# charging_circuit.net
KiCad netlist of a schematic drawn in EAGLE
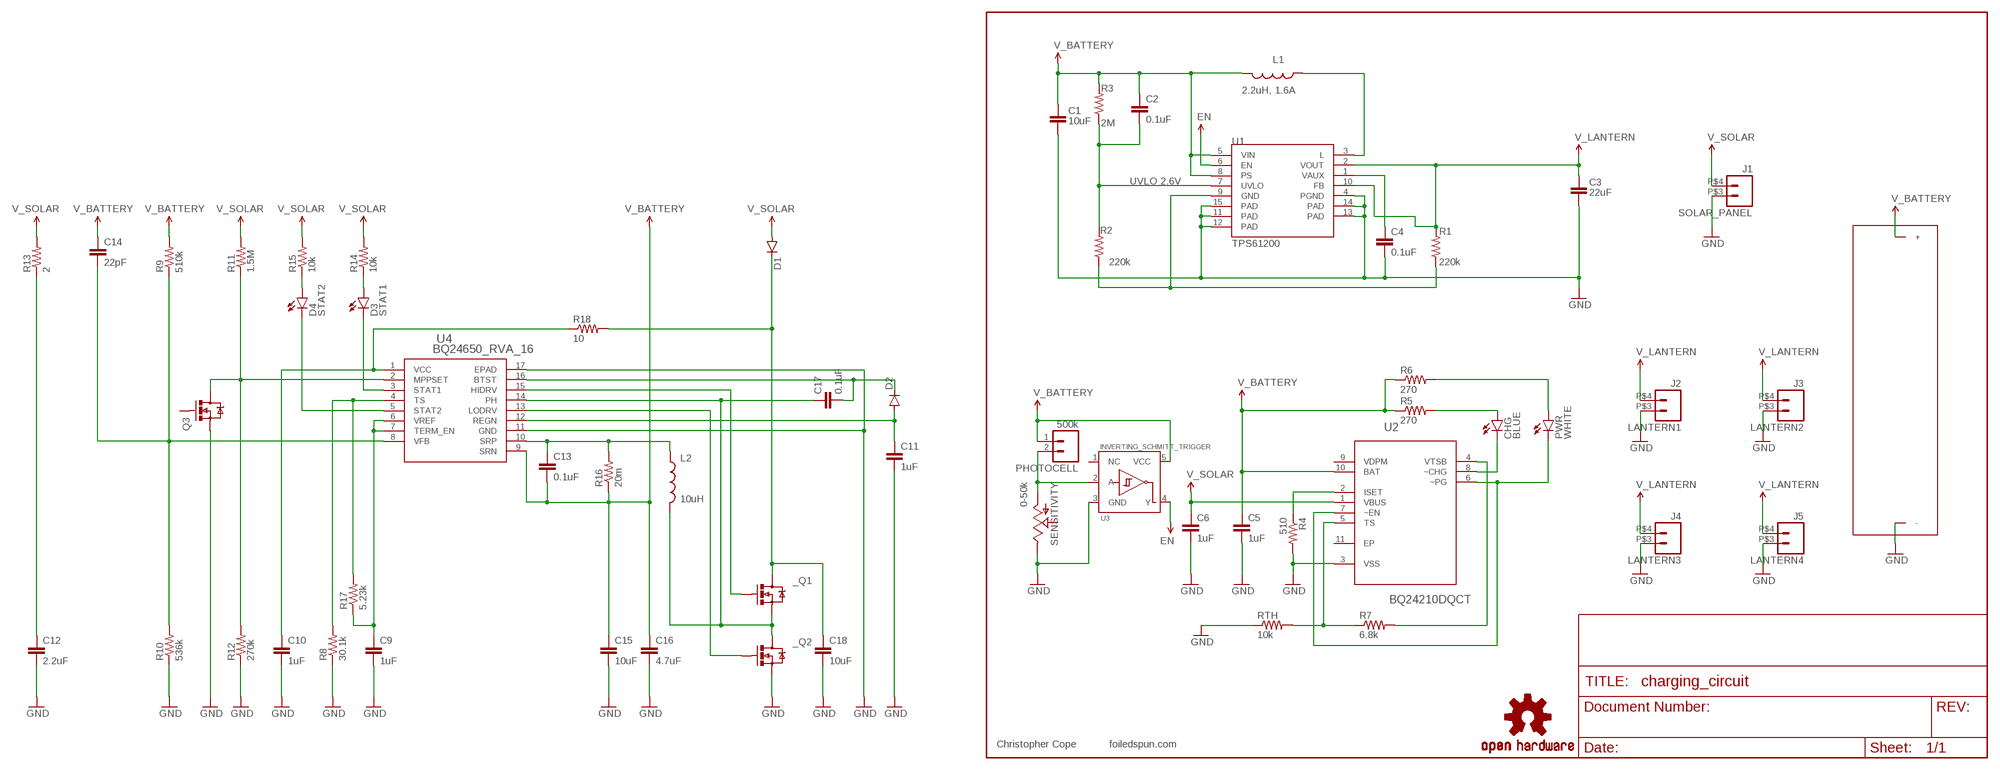
[diagram p0: schematic, sheet 1]

(export (version "E")
  (design (tool "Eeschema 10.0.6"))
  (components
    (comp (ref "C1")
      (value "10uF")
      (footprint "eagle-import:1206")
      (libsource (lib "eagle-import") (part "CAP1206"))
    )
    (comp (ref "C2")
      (value "0.1uF")
      (footprint "eagle-import:0402-CAP")
      (libsource (lib "eagle-import") (part "CAP0402-CAP"))
    )
    (comp (ref "C3")
      (value "22uF")
      (footprint "eagle-import:0805")
      (libsource (lib "eagle-import") (part "CAP0805"))
    )
    (comp (ref "C4")
      (value "0.1uF")
      (footprint "eagle-import:0402-CAP")
      (libsource (lib "eagle-import") (part "CAP0402-CAP"))
    )
    (comp (ref "C5")
      (value "1uF")
      (footprint "eagle-import:0805")
      (libsource (lib "eagle-import") (part "1UF-25V-10%(0805)"))
    )
    (comp (ref "C6")
      (value "1uF")
      (footprint "eagle-import:0805")
      (libsource (lib "eagle-import") (part "1UF-25V-10%(0805)"))
    )
    (comp (ref "C9")
      (value "1uF")
      (footprint "eagle-import:0402-CAP")
      (libsource (lib "eagle-import") (part "CAP0402-CAP"))
    )
    (comp (ref "C10")
      (value "1uF")
      (footprint "eagle-import:0402-CAP")
      (libsource (lib "eagle-import") (part "CAP0402-CAP"))
    )
    (comp (ref "C11")
      (value "1uF")
      (footprint "eagle-import:0402-CAP")
      (libsource (lib "eagle-import") (part "CAP0402-CAP"))
    )
    (comp (ref "C12")
      (value "2.2uF")
      (footprint "eagle-import:0402-CAP")
      (libsource (lib "eagle-import") (part "CAP0402-CAP"))
    )
    (comp (ref "C13")
      (value "0.1uF")
      (footprint "eagle-import:0805")
      (libsource (lib "eagle-import") (part "SparkFun-Passives_CAP0805"))
    )
    (comp (ref "C14")
      (value "22pF")
      (footprint "eagle-import:0603-CAP")
      (libsource (lib "eagle-import") (part "SparkFun-Passives_CAP0603-CAP"))
    )
    (comp (ref "C15")
      (value "10uF")
      (footprint "eagle-import:1210")
      (libsource (lib "eagle-import") (part "SparkFun-Passives_CAP1210"))
    )
    (comp (ref "C16")
      (value "4.7uF")
      (footprint "eagle-import:1210")
      (libsource (lib "eagle-import") (part "SparkFun-Passives_CAP1210"))
    )
    (comp (ref "C17")
      (value "0.1uF")
      (footprint "eagle-import:0805")
      (libsource (lib "eagle-import") (part "SparkFun-Passives_CAP0805"))
    )
    (comp (ref "C18")
      (value "10uF")
      (footprint "eagle-import:1210")
      (libsource (lib "eagle-import") (part "SparkFun-Passives_CAP1210"))
    )
    (comp (ref "CHG")
      (value "BLUE")
      (footprint "eagle-import:LED-0603")
      (libsource (lib "eagle-import") (part "LED0603"))
    )
    (comp (ref "D1")
      (value "DIODEPDS1040")
      (footprint "eagle-import:POWERDI-5")
      (libsource (lib "eagle-import") (part "DIODEPDS1040"))
    )
    (comp (ref "D2")
      (value "DIODESOT23")
      (footprint "eagle-import:SOT23-3")
      (libsource (lib "eagle-import") (part "SparkFun-DiscreteSemi_DIODESOT23"))
    )
    (comp (ref "D3")
      (value "STAT1")
      (footprint "eagle-import:LED-0603")
      (libsource (lib "eagle-import") (part "LED-GREEN0603"))
    )
    (comp (ref "D4")
      (value "STAT2")
      (footprint "eagle-import:LED-0603")
      (libsource (lib "eagle-import") (part "LED-GREEN0603"))
    )
    (comp (ref "L1")
      (value "2.2uH, 1.6A")
      (footprint "eagle-import:1210")
      (libsource (lib "eagle-import") (part "INDUCTOR1210"))
    )
    (comp (ref "L2")
      (value "10uH")
      (footprint "eagle-import:IHLP-2525CZ-01")
      (libsource (lib "eagle-import") (part "INDUCTORIHLP-2525CZ-01"))
    )
    (comp (ref "LANTERN1")
      (value "J2")
      (footprint "eagle-import:2-1445100-2")
      (libsource (lib "eagle-import") (part "MICRO_MATE-N-LOCK"))
    )
    (comp (ref "LANTERN2")
      (value "J3")
      (footprint "eagle-import:2-1445100-2")
      (libsource (lib "eagle-import") (part "MICRO_MATE-N-LOCK"))
    )
    (comp (ref "LANTERN3")
      (value "J4")
      (footprint "eagle-import:2-1445100-2")
      (libsource (lib "eagle-import") (part "MICRO_MATE-N-LOCK"))
    )
    (comp (ref "LANTERN4")
      (value "J5")
      (footprint "eagle-import:2-1445100-2")
      (libsource (lib "eagle-import") (part "MICRO_MATE-N-LOCK"))
    )
    (comp (ref "LOGO2")
      (value "OSHW-LOGOL")
      (footprint "eagle-import:OSHW-LOGO-L")
      (libsource (lib "eagle-import") (part "OSHW-LOGOL"))
    )
    (comp (ref "PHOTOCELL")
      (value "500k")
      (footprint "eagle-import:1X02_SMD")
      (libsource (lib "eagle-import") (part "M021X02_SMD"))
    )
    (comp (ref "PWR")
      (value "WHITE")
      (footprint "eagle-import:LED-0603")
      (libsource (lib "eagle-import") (part "LED0603"))
    )
    (comp (ref "Q3")
      (value "MOSFET-NCHANNEL")
      (footprint "eagle-import:SOT23-3")
      (libsource (lib "eagle-import") (part "MOSFET-NCHANNEL"))
    )
    (comp (ref "R1")
      (value "220k")
      (footprint "eagle-import:0402-RES")
      (libsource (lib "eagle-import") (part "RESISTOR0402-RES"))
    )
    (comp (ref "R2")
      (value "220k")
      (footprint "eagle-import:0402-RES")
      (libsource (lib "eagle-import") (part "RESISTOR0402-RES"))
    )
    (comp (ref "R3")
      (value "2M")
      (footprint "eagle-import:0402-RES")
      (libsource (lib "eagle-import") (part "RESISTOR0402-RES"))
    )
    (comp (ref "R4")
      (value "510")
      (footprint "eagle-import:0402-RES")
      (libsource (lib "eagle-import") (part "SparkFun-Resistors_RESISTOR0402-RES"))
    )
    (comp (ref "R5")
      (value "270")
      (footprint "eagle-import:0402-RES")
      (libsource (lib "eagle-import") (part "SparkFun-Resistors_RESISTOR0402-RES"))
    )
    (comp (ref "R6")
      (value "270")
      (footprint "eagle-import:0402-RES")
      (libsource (lib "eagle-import") (part "SparkFun-Resistors_RESISTOR0402-RES"))
    )
    (comp (ref "R7")
      (value "6.8k")
      (footprint "eagle-import:0402-RES")
      (libsource (lib "eagle-import") (part "SparkFun-Resistors_RESISTOR0402-RES"))
    )
    (comp (ref "R8")
      (value "30.1k")
      (footprint "eagle-import:0402-RES")
      (libsource (lib "eagle-import") (part "SparkFun-Passives_RESISTOR0402-RES"))
    )
    (comp (ref "R9")
      (value "510k")
      (footprint "eagle-import:0402-RES")
      (libsource (lib "eagle-import") (part "RESISTOR0402-RES"))
    )
    (comp (ref "R10")
      (value "536k")
      (footprint "eagle-import:0402-RES")
      (libsource (lib "eagle-import") (part "RESISTOR0402-RES"))
    )
    (comp (ref "R11")
      (value "1.5M")
      (footprint "eagle-import:0402-RES")
      (libsource (lib "eagle-import") (part "RESISTOR0402-RES"))
    )
    (comp (ref "R12")
      (value "270k")
      (footprint "eagle-import:0402-RES")
      (libsource (lib "eagle-import") (part "RESISTOR0402-RES"))
    )
    (comp (ref "R13")
      (value "2")
      (footprint "eagle-import:0402-RES")
      (libsource (lib "eagle-import") (part "RESISTOR0402-RES"))
    )
    (comp (ref "R14")
      (value "10k")
      (footprint "eagle-import:0402-RES")
      (libsource (lib "eagle-import") (part "SparkFun-Passives_RESISTOR0402-RES"))
    )
    (comp (ref "R15")
      (value "10k")
      (footprint "eagle-import:0402-RES")
      (libsource (lib "eagle-import") (part "SparkFun-Passives_RESISTOR0402-RES"))
    )
    (comp (ref "R16")
      (value "20m")
      (footprint "eagle-import:1206")
      (libsource (lib "eagle-import") (part "SparkFun-Passives_RESISTOR1206"))
    )
    (comp (ref "R17")
      (value "5.23k")
      (footprint "eagle-import:0402-RES")
      (libsource (lib "eagle-import") (part "SparkFun-Passives_RESISTOR0402-RES"))
    )
    (comp (ref "R18")
      (value "10")
      (footprint "eagle-import:1206")
      (libsource (lib "eagle-import") (part "SparkFun-Passives_RESISTOR1206"))
    )
    (comp (ref "RTH")
      (value "10k")
      (footprint "eagle-import:0402-RES")
      (libsource (lib "eagle-import") (part "SparkFun-Resistors_RESISTOR0402-RES"))
    )
    (comp (ref "SENSITIVITY")
      (value "0-50k")
      (footprint "eagle-import:TRIM_POT-SMD")
      (libsource (lib "eagle-import") (part "POTTRIM_POT-SMD"))
    )
    (comp (ref "SOLAR_PANEL")
      (value "J1")
      (footprint "eagle-import:2-1445100-2")
      (libsource (lib "eagle-import") (part "MICRO_MATE-N-LOCK"))
    )
    (comp (ref "U$1")
      (value "18650-HOLDER")
      (footprint "eagle-import:18650")
      (libsource (lib "eagle-import") (part "18650-HOLDER"))
    )
    (comp (ref "U1")
      (value "TPS61200")
      (footprint "eagle-import:QFN-10_PAD")
      (libsource (lib "eagle-import") (part "TPS61200"))
    )
    (comp (ref "U2")
      (value "BQ24210DQCT")
      (footprint "eagle-import:SON50P200X300X80-11N")
      (libsource (lib "eagle-import") (part "BQ24210DQCT"))
    )
    (comp (ref "U3")
      (value "INVERTING_SCHMITT_TRIGGER")
      (footprint "eagle-import:SC-70-5(DCK)")
      (libsource (lib "eagle-import") (part "INVERTING_SCHMITT_TRIGGER"))
    )
    (comp (ref "U4")
      (value "BQ24650_RVA_16")
      (footprint "eagle-import:RVA16_2P14X2P14")
      (fields
        (field (name "GENERIC_PART_NUMBER") "BQ24650")
        (field (name "MANUFACTURER") "Texas Instruments")
      )
      (libsource (lib "eagle-import") (part "BQ24650_RVA_16"))
    )
    (comp (ref "_")
      (value "MOSFET-DUAL_NCHANNEL")
      (footprint "eagle-import:POWERPAK_SO-8")
      (libsource (lib "eagle-import") (part "MOSFET-DUAL_NCHANNEL"))
    )
  )
  (nets
    (net (code "1") (name "EN") (class "Default")
      (node (ref "U1") (pin "6") (pinfunction "EN_6") (pintype "input"))
      (node (ref "U3") (pin "4") (pinfunction "Y_4") (pintype "bidirectional"))
    )
    (net (code "2") (name "GND") (class "Default")
      (node (ref "C1") (pin "2") (pinfunction "2_2") (pintype "passive"))
      (node (ref "C10") (pin "2") (pinfunction "2_2") (pintype "passive"))
      (node (ref "C11") (pin "2") (pinfunction "2_2") (pintype "passive"))
      (node (ref "C12") (pin "2") (pinfunction "2_2") (pintype "passive"))
      (node (ref "C15") (pin "2") (pinfunction "2_2") (pintype "passive"))
      (node (ref "C16") (pin "2") (pinfunction "2_2") (pintype "passive"))
      (node (ref "C18") (pin "2") (pinfunction "2_2") (pintype "passive"))
      (node (ref "C3") (pin "2") (pinfunction "2_2") (pintype "passive"))
      (node (ref "C4") (pin "2") (pinfunction "2_2") (pintype "passive"))
      (node (ref "C5") (pin "2") (pinfunction "2_2") (pintype "passive"))
      (node (ref "C6") (pin "2") (pinfunction "2_2") (pintype "passive"))
      (node (ref "C9") (pin "2") (pinfunction "2_2") (pintype "passive"))
      (node (ref "LANTERN1") (pin "P$3") (pinfunction "2_P$3") (pintype "passive"))
      (node (ref "LANTERN2") (pin "P$3") (pinfunction "2_P$3") (pintype "passive"))
      (node (ref "LANTERN3") (pin "P$3") (pinfunction "2_P$3") (pintype "passive"))
      (node (ref "LANTERN4") (pin "P$3") (pinfunction "2_P$3") (pintype "passive"))
      (node (ref "Q3") (pin "2") (pinfunction "S_2") (pintype "passive"))
      (node (ref "R10") (pin "1") (pinfunction "1_1") (pintype "passive"))
      (node (ref "R12") (pin "1") (pinfunction "1_1") (pintype "passive"))
      (node (ref "R4") (pin "2") (pinfunction "2_2") (pintype "passive"))
      (node (ref "R8") (pin "1") (pinfunction "1_1") (pintype "passive"))
      (node (ref "RTH") (pin "1") (pinfunction "1_1") (pintype "passive"))
      (node (ref "SENSITIVITY") (pin "P$3") (pinfunction "E_P$3") (pintype "passive"))
      (node (ref "SOLAR_PANEL") (pin "P$3") (pinfunction "2_P$3") (pintype "passive"))
      (node (ref "U$1") (pin "-") (pinfunction "-_-") (pintype "power_in"))
      (node (ref "U1") (pin "11") (pinfunction "PAD_11") (pintype "power_in"))
      (node (ref "U1") (pin "12") (pinfunction "PAD_12") (pintype "power_in"))
      (node (ref "U1") (pin "13") (pinfunction "PAD_13") (pintype "power_in"))
      (node (ref "U1") (pin "14") (pinfunction "PAD_14") (pintype "power_in"))
      (node (ref "U1") (pin "15") (pinfunction "PAD_15") (pintype "power_in"))
      (node (ref "U1") (pin "4") (pinfunction "PGND_4") (pintype "power_in"))
      (node (ref "U2") (pin "3") (pinfunction "VSS_3") (pintype "passive"))
      (node (ref "U3") (pin "3") (pinfunction "GND_3") (pintype "bidirectional"))
      (node (ref "U4") (pin "11") (pinfunction "GND_11") (pintype "power_in"))
      (node (ref "U4") (pin "17") (pinfunction "EPAD_17") (pintype "power_in"))
      (node (ref "_") (pin "P$3$S2") (pinfunction "S_P$3$S2") (pintype "passive"))
    )
    (net (code "3") (name "Net-(C12-Pad1)") (class "Default")
      (node (ref "C12") (pin "1") (pinfunction "1_1") (pintype "passive"))
      (node (ref "R13") (pin "1") (pinfunction "1_1") (pintype "passive"))
    )
    (net (code "4") (name "Net-(CHG-PadA)") (class "Default")
      (node (ref "CHG") (pin "A") (pinfunction "A_A") (pintype "passive"))
      (node (ref "R5") (pin "2") (pinfunction "2_2") (pintype "passive"))
    )
    (net (code "5") (name "Net-(D1-C)") (class "Default")
      (node (ref "C18") (pin "1") (pinfunction "1_1") (pintype "passive"))
      (node (ref "D1") (pin "P$3") (pinfunction "C_P$3") (pintype "passive"))
      (node (ref "R18") (pin "2") (pinfunction "2_2") (pintype "passive"))
      (node (ref "_") (pin "P$7$D1") (pinfunction "D_P$7$D1") (pintype "passive"))
      (node (ref "_") (pin "P$8$D1") (pinfunction "D_P$8$D1") (pintype "passive"))
      (node (ref "_") (pin "P$D1") (pinfunction "D_P$D1") (pintype "passive"))
    )
    (net (code "6") (name "Net-(D2-A)") (class "Default")
      (node (ref "C11") (pin "1") (pinfunction "1_1") (pintype "passive"))
      (node (ref "D2") (pin "1") (pinfunction "A_1") (pintype "passive"))
      (node (ref "U4") (pin "12") (pinfunction "REGN_12") (pintype "power_in"))
    )
    (net (code "7") (name "Net-(D2-C)") (class "Default")
      (node (ref "C17") (pin "2") (pinfunction "2_2") (pintype "passive"))
      (node (ref "D2") (pin "3") (pinfunction "C_3") (pintype "passive"))
      (node (ref "U4") (pin "16") (pinfunction "BTST_16") (pintype "power_in"))
    )
    (net (code "8") (name "Net-(D3-PadA)") (class "Default")
      (node (ref "D3") (pin "A") (pinfunction "A_A") (pintype "passive"))
      (node (ref "R14") (pin "1") (pinfunction "1_1") (pintype "passive"))
    )
    (net (code "9") (name "Net-(D4-PadA)") (class "Default")
      (node (ref "D4") (pin "A") (pinfunction "A_A") (pintype "passive"))
      (node (ref "R15") (pin "1") (pinfunction "1_1") (pintype "passive"))
    )
    (net (code "10") (name "Net-(L2-1)") (class "Default")
      (node (ref "C13") (pin "1") (pinfunction "1_1") (pintype "passive"))
      (node (ref "L2") (pin "P$1") (pinfunction "1_P$1") (pintype "passive"))
      (node (ref "R16") (pin "2") (pinfunction "2_2") (pintype "passive"))
      (node (ref "U4") (pin "10") (pinfunction "SRP_10") (pintype "bidirectional"))
    )
    (net (code "11") (name "Net-(L2-2)") (class "Default")
      (node (ref "C17") (pin "1") (pinfunction "1_1") (pintype "passive"))
      (node (ref "L2") (pin "P$2") (pinfunction "2_P$2") (pintype "passive"))
      (node (ref "U4") (pin "14") (pinfunction "PH_14") (pintype "power_in"))
      (node (ref "_") (pin "P$1$S1") (pinfunction "S_P$1$S1") (pintype "passive"))
      (node (ref "_") (pin "P$5$D2") (pinfunction "D_P$5$D2") (pintype "passive"))
      (node (ref "_") (pin "P$6$D2") (pinfunction "D_P$6$D2") (pintype "passive"))
      (node (ref "_") (pin "P$D2") (pinfunction "D_P$D2") (pintype "passive"))
    )
    (net (code "12") (name "Net-(PWR-PadA)") (class "Default")
      (node (ref "PWR") (pin "A") (pinfunction "A_A") (pintype "passive"))
      (node (ref "R6") (pin "2") (pinfunction "2_2") (pintype "passive"))
    )
    (net (code "13") (name "Net-(Q3-D)") (class "Default")
      (node (ref "Q3") (pin "3") (pinfunction "D_3") (pintype "passive"))
      (node (ref "R11") (pin "1") (pinfunction "1_1") (pintype "passive"))
      (node (ref "R12") (pin "2") (pinfunction "2_2") (pintype "passive"))
      (node (ref "U4") (pin "2") (pinfunction "MPPSET_2") (pintype "input"))
    )
    (net (code "14") (name "Net-(SENSITIVITY-A)") (class "Default")
      (node (ref "PHOTOCELL") (pin "2") (pinfunction "2_2") (pintype "passive"))
      (node (ref "SENSITIVITY") (pin "P$1") (pinfunction "A_P$1") (pintype "passive"))
      (node (ref "U3") (pin "2") (pinfunction "A_2") (pintype "bidirectional"))
    )
    (net (code "15") (name "Net-(U1-GND)") (class "Default")
      (node (ref "R1") (pin "1") (pinfunction "1_1") (pintype "passive"))
      (node (ref "R2") (pin "1") (pinfunction "1_1") (pintype "passive"))
      (node (ref "U1") (pin "9") (pinfunction "GND_9") (pintype "power_in"))
    )
    (net (code "16") (name "Net-(U1-L)") (class "Default")
      (node (ref "L1") (pin "1") (pinfunction "1_1") (pintype "passive"))
      (node (ref "U1") (pin "3") (pinfunction "L_3") (pintype "passive"))
    )
    (net (code "17") (name "Net-(U1-UVLO)") (class "Default")
      (node (ref "C2") (pin "2") (pinfunction "2_2") (pintype "passive"))
      (node (ref "R2") (pin "2") (pinfunction "2_2") (pintype "passive"))
      (node (ref "R3") (pin "1") (pinfunction "1_1") (pintype "passive"))
      (node (ref "U1") (pin "7") (pinfunction "UVLO_7") (pintype "passive"))
    )
    (net (code "18") (name "Net-(U1-VAUX)") (class "Default")
      (node (ref "C4") (pin "1") (pinfunction "1_1") (pintype "passive"))
      (node (ref "U1") (pin "1") (pinfunction "VAUX_1") (pintype "passive"))
    )
    (net (code "19") (name "Net-(U2-ISET)") (class "Default")
      (node (ref "R4") (pin "1") (pinfunction "1_1") (pintype "passive"))
      (node (ref "U2") (pin "2") (pinfunction "ISET_2") (pintype "input"))
    )
    (net (code "20") (name "Net-(U2-TS)") (class "Default")
      (node (ref "R7") (pin "1") (pinfunction "1_1") (pintype "passive"))
      (node (ref "RTH") (pin "2") (pinfunction "2_2") (pintype "passive"))
      (node (ref "U2") (pin "5") (pinfunction "TS_5") (pintype "input"))
    )
    (net (code "21") (name "Net-(U2-VTSB)") (class "Default")
      (node (ref "R7") (pin "2") (pinfunction "2_2") (pintype "passive"))
      (node (ref "U2") (pin "4") (pinfunction "VTSB_4") (pintype "output"))
    )
    (net (code "22") (name "Net-(U2-~{CHG})") (class "Default")
      (node (ref "CHG") (pin "C") (pinfunction "C_C") (pintype "passive"))
      (node (ref "U2") (pin "8") (pinfunction "~{CHG}_8") (pintype "output"))
    )
    (net (code "23") (name "Net-(U2-~{EN})") (class "Default")
      (node (ref "PWR") (pin "C") (pinfunction "C_C") (pintype "passive"))
      (node (ref "U2") (pin "6") (pinfunction "~{PG}_6") (pintype "output"))
      (node (ref "U2") (pin "7") (pinfunction "~{EN}_7") (pintype "input"))
    )
    (net (code "24") (name "Net-(U4-HIDRV)") (class "Default")
      (node (ref "U4") (pin "15") (pinfunction "HIDRV_15") (pintype "output"))
      (node (ref "_") (pin "P$2$G1") (pinfunction "G_P$2$G1") (pintype "passive"))
    )
    (net (code "25") (name "Net-(U4-LODRV)") (class "Default")
      (node (ref "U4") (pin "13") (pinfunction "LODRV_13") (pintype "output"))
      (node (ref "_") (pin "P$4$G2") (pinfunction "G_P$4$G2") (pintype "passive"))
    )
    (net (code "26") (name "Net-(U4-STAT1)") (class "Default")
      (node (ref "D3") (pin "C") (pinfunction "C_C") (pintype "passive"))
      (node (ref "U4") (pin "3") (pinfunction "STAT1_3") (pintype "output"))
    )
    (net (code "27") (name "Net-(U4-STAT2)") (class "Default")
      (node (ref "D4") (pin "C") (pinfunction "C_C") (pintype "passive"))
      (node (ref "U4") (pin "5") (pinfunction "STAT2_5") (pintype "output"))
    )
    (net (code "28") (name "Net-(U4-TERM_EN)") (class "Default")
      (node (ref "C9") (pin "1") (pinfunction "1_1") (pintype "passive"))
      (node (ref "R17") (pin "1") (pinfunction "1_1") (pintype "passive"))
      (node (ref "U4") (pin "6") (pinfunction "VREF_6") (pintype "power_in"))
      (node (ref "U4") (pin "7") (pinfunction "TERM_EN_7") (pintype "input"))
    )
    (net (code "29") (name "Net-(U4-TS)") (class "Default")
      (node (ref "R17") (pin "2") (pinfunction "2_2") (pintype "passive"))
      (node (ref "R8") (pin "2") (pinfunction "2_2") (pintype "passive"))
      (node (ref "U4") (pin "4") (pinfunction "TS_4") (pintype "input"))
    )
    (net (code "30") (name "Net-(U4-VCC)") (class "Default")
      (node (ref "C10") (pin "1") (pinfunction "1_1") (pintype "passive"))
      (node (ref "R18") (pin "1") (pinfunction "1_1") (pintype "passive"))
      (node (ref "U4") (pin "1") (pinfunction "VCC_1") (pintype "power_in"))
    )
    (net (code "31") (name "Net-(U4-VFB)") (class "Default")
      (node (ref "C14") (pin "2") (pinfunction "2_2") (pintype "passive"))
      (node (ref "R10") (pin "2") (pinfunction "2_2") (pintype "passive"))
      (node (ref "R9") (pin "1") (pinfunction "1_1") (pintype "passive"))
      (node (ref "U4") (pin "8") (pinfunction "VFB_8") (pintype "input"))
    )
    (net (code "32") (name "V_BATTERY") (class "Default")
      (node (ref "C1") (pin "1") (pinfunction "1_1") (pintype "passive"))
      (node (ref "C13") (pin "2") (pinfunction "2_2") (pintype "passive"))
      (node (ref "C14") (pin "1") (pinfunction "1_1") (pintype "passive"))
      (node (ref "C15") (pin "1") (pinfunction "1_1") (pintype "passive"))
      (node (ref "C16") (pin "1") (pinfunction "1_1") (pintype "passive"))
      (node (ref "C2") (pin "1") (pinfunction "1_1") (pintype "passive"))
      (node (ref "C5") (pin "1") (pinfunction "1_1") (pintype "passive"))
      (node (ref "L1") (pin "2") (pinfunction "2_2") (pintype "passive"))
      (node (ref "PHOTOCELL") (pin "1") (pinfunction "1_1") (pintype "passive"))
      (node (ref "R16") (pin "1") (pinfunction "1_1") (pintype "passive"))
      (node (ref "R3") (pin "2") (pinfunction "2_2") (pintype "passive"))
      (node (ref "R5") (pin "1") (pinfunction "1_1") (pintype "passive"))
      (node (ref "R6") (pin "1") (pinfunction "1_1") (pintype "passive"))
      (node (ref "R9") (pin "2") (pinfunction "2_2") (pintype "passive"))
      (node (ref "U$1") (pin "+") (pinfunction "+_+") (pintype "power_in"))
      (node (ref "U1") (pin "5") (pinfunction "VIN_5") (pintype "power_in"))
      (node (ref "U1") (pin "8") (pinfunction "PS_8") (pintype "input"))
      (node (ref "U2") (pin "10") (pinfunction "BAT_10") (pintype "bidirectional"))
      (node (ref "U3") (pin "5") (pinfunction "VCC_5") (pintype "bidirectional"))
      (node (ref "U4") (pin "9") (pinfunction "SRN_9") (pintype "input"))
    )
    (net (code "33") (name "V_LANTERN") (class "Default")
      (node (ref "C3") (pin "1") (pinfunction "1_1") (pintype "passive"))
      (node (ref "LANTERN1") (pin "P$4") (pinfunction "1_P$4") (pintype "passive"))
      (node (ref "LANTERN2") (pin "P$4") (pinfunction "1_P$4") (pintype "passive"))
      (node (ref "LANTERN3") (pin "P$4") (pinfunction "1_P$4") (pintype "passive"))
      (node (ref "LANTERN4") (pin "P$4") (pinfunction "1_P$4") (pintype "passive"))
      (node (ref "R1") (pin "2") (pinfunction "2_2") (pintype "passive"))
      (node (ref "U1") (pin "10") (pinfunction "FB_10") (pintype "passive"))
      (node (ref "U1") (pin "2") (pinfunction "VOUT_2") (pintype "passive"))
    )
    (net (code "34") (name "V_SOLAR") (class "Default")
      (node (ref "C6") (pin "1") (pinfunction "1_1") (pintype "passive"))
      (node (ref "D1") (pin "P$1") (pinfunction "A_P$1") (pintype "passive"))
      (node (ref "D1") (pin "P$2") (pinfunction "A_P$2") (pintype "passive"))
      (node (ref "R11") (pin "2") (pinfunction "2_2") (pintype "passive"))
      (node (ref "R13") (pin "2") (pinfunction "2_2") (pintype "passive"))
      (node (ref "R14") (pin "2") (pinfunction "2_2") (pintype "passive"))
      (node (ref "R15") (pin "2") (pinfunction "2_2") (pintype "passive"))
      (node (ref "SOLAR_PANEL") (pin "P$4") (pinfunction "1_P$4") (pintype "passive"))
      (node (ref "U2") (pin "1") (pinfunction "VBUS_1") (pintype "bidirectional"))
    )
    (net (code "35") (name "unconnected-(Q3-G-Pad1)") (class "Default")
      (node (ref "Q3") (pin "1") (pinfunction "G_1") (pintype "passive"))
    )
    (net (code "36") (name "unconnected-(SENSITIVITY-S-PadP$2)") (class "Default")
      (node (ref "SENSITIVITY") (pin "P$2") (pinfunction "S_P$2") (pintype "passive"))
    )
    (net (code "37") (name "unconnected-(U2-EP-Pad11)") (class "Default")
      (node (ref "U2") (pin "11") (pinfunction "EP_11") (pintype "passive"))
    )
    (net (code "38") (name "unconnected-(U2-VDPM-Pad9)") (class "Default")
      (node (ref "U2") (pin "9") (pinfunction "VDPM_9") (pintype "input"))
    )
    (net (code "39") (name "unconnected-(U3-NC-Pad1)") (class "Default")
      (node (ref "U3") (pin "1") (pinfunction "NC_1") (pintype "bidirectional"))
    )
  )
)
